# 8050a_led.net
KiCad netlist of a schematic drawn in EAGLE
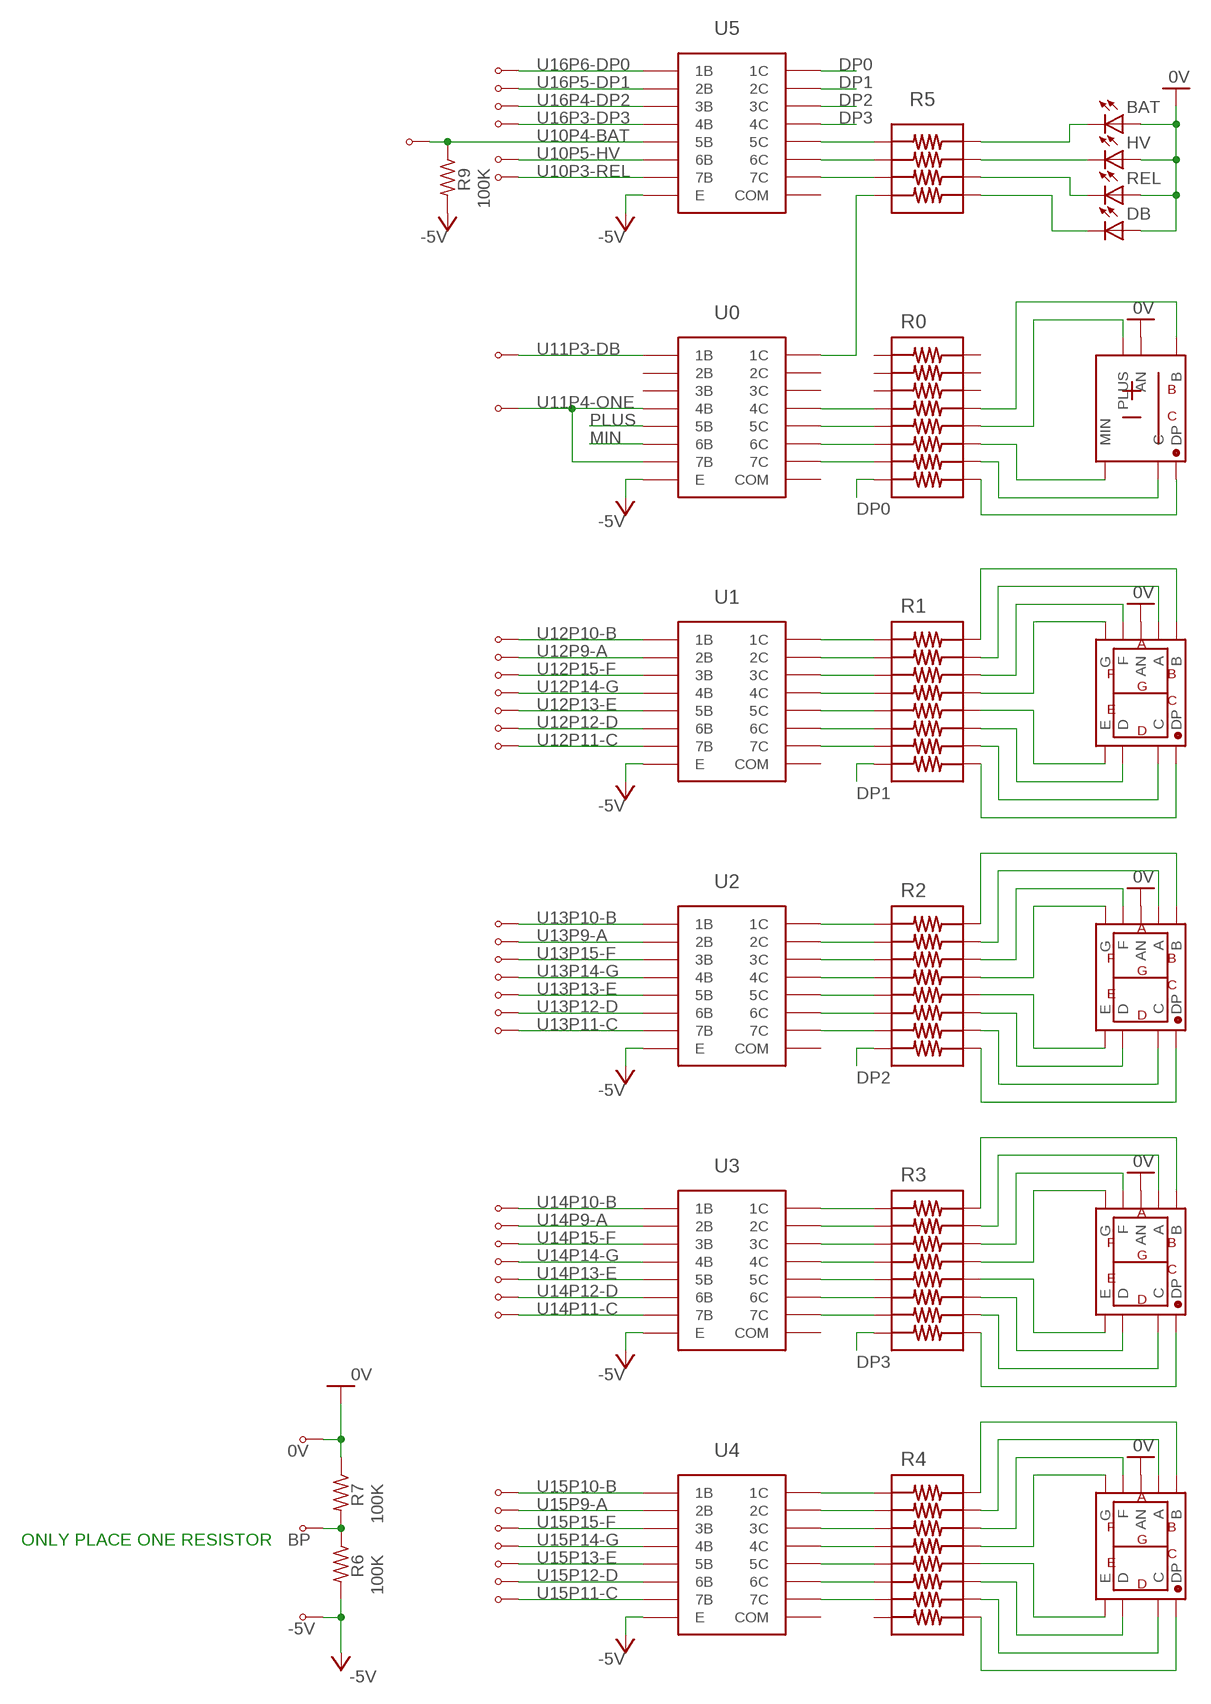
[diagram p0: schematic, sheet 1]

(export (version "E")
  (design (tool "Eeschema 10.0.6"))
  (components
    (comp (ref "BAT")
      (value "LED_0805")
      (footprint "eagle-import:0805_POL")
      (libsource (lib "eagle-import") (part "LED_0805"))
    )
    (comp (ref "D0")
      (value "LUMEX_LDF-A5616RI")
      (footprint "eagle-import:LUMEX_LDS-A516RI")
      (libsource (lib "eagle-import") (part "LUMEX_LDF-A5616RI"))
    )
    (comp (ref "D1")
      (value "LUMEX_LDS-A516RI")
      (footprint "eagle-import:LUMEX_LDS-A516RI")
      (libsource (lib "eagle-import") (part "LUMEX_LDS-A516RI"))
    )
    (comp (ref "D2")
      (value "LUMEX_LDS-A516RI")
      (footprint "eagle-import:LUMEX_LDS-A516RI")
      (libsource (lib "eagle-import") (part "LUMEX_LDS-A516RI"))
    )
    (comp (ref "D3")
      (value "LUMEX_LDS-A516RI")
      (footprint "eagle-import:LUMEX_LDS-A516RI")
      (libsource (lib "eagle-import") (part "LUMEX_LDS-A516RI"))
    )
    (comp (ref "D4")
      (value "LUMEX_LDS-A516RI")
      (footprint "eagle-import:LUMEX_LDS-A516RI")
      (libsource (lib "eagle-import") (part "LUMEX_LDS-A516RI"))
    )
    (comp (ref "DB")
      (value "LED_0805")
      (footprint "eagle-import:0805_POL")
      (libsource (lib "eagle-import") (part "LED_0805"))
    )
    (comp (ref "HV")
      (value "LED_0805")
      (footprint "eagle-import:0805_POL")
      (libsource (lib "eagle-import") (part "LED_0805"))
    )
    (comp (ref "R0")
      (value "BOURNS_CAT16-XXXJ8")
      (footprint "eagle-import:BOURNS_CAT16-J8")
      (libsource (lib "eagle-import") (part "BOURNS_CAT16-XXXJ8"))
    )
    (comp (ref "R1")
      (value "BOURNS_CAT16-XXXJ8")
      (footprint "eagle-import:BOURNS_CAT16-J8")
      (libsource (lib "eagle-import") (part "BOURNS_CAT16-XXXJ8"))
    )
    (comp (ref "R2")
      (value "BOURNS_CAT16-XXXJ8")
      (footprint "eagle-import:BOURNS_CAT16-J8")
      (libsource (lib "eagle-import") (part "BOURNS_CAT16-XXXJ8"))
    )
    (comp (ref "R3")
      (value "BOURNS_CAT16-XXXJ8")
      (footprint "eagle-import:BOURNS_CAT16-J8")
      (libsource (lib "eagle-import") (part "BOURNS_CAT16-XXXJ8"))
    )
    (comp (ref "R4")
      (value "BOURNS_CAT16-XXXJ8")
      (footprint "eagle-import:BOURNS_CAT16-J8")
      (libsource (lib "eagle-import") (part "BOURNS_CAT16-XXXJ8"))
    )
    (comp (ref "R5")
      (value "BOURNS_CAT16XXXJ4")
      (footprint "eagle-import:BOURNS_CAT16-J4")
      (libsource (lib "eagle-import") (part "BOURNS_CAT16XXXJ4"))
    )
    (comp (ref "R6")
      (value "100K")
      (footprint "eagle-import:0603")
      (libsource (lib "eagle-import") (part "R_0603"))
    )
    (comp (ref "R7")
      (value "100K")
      (footprint "eagle-import:0603")
      (libsource (lib "eagle-import") (part "R_0603"))
    )
    (comp (ref "R9")
      (value "100K")
      (footprint "eagle-import:0603")
      (libsource (lib "eagle-import") (part "R_0603"))
    )
    (comp (ref "REL")
      (value "LED_0805")
      (footprint "eagle-import:0805_POL")
      (libsource (lib "eagle-import") (part "LED_0805"))
    )
    (comp (ref "TP1")
      (value "KEYSTONE_500X")
      (footprint "eagle-import:KEYSTONE_500X")
      (libsource (lib "eagle-import") (part "KEYSTONE_500X"))
    )
    (comp (ref "TP2")
      (value "KEYSTONE_500X")
      (footprint "eagle-import:KEYSTONE_500X")
      (libsource (lib "eagle-import") (part "KEYSTONE_500X"))
    )
    (comp (ref "TP3")
      (value "KEYSTONE_500X")
      (footprint "eagle-import:KEYSTONE_500X")
      (libsource (lib "eagle-import") (part "KEYSTONE_500X"))
    )
    (comp (ref "TP4")
      (value "KEYSTONE_500X")
      (footprint "eagle-import:KEYSTONE_500X")
      (libsource (lib "eagle-import") (part "KEYSTONE_500X"))
    )
    (comp (ref "TP5")
      (value "KEYSTONE_500X")
      (footprint "eagle-import:KEYSTONE_500X")
      (libsource (lib "eagle-import") (part "KEYSTONE_500X"))
    )
    (comp (ref "TP6")
      (value "KEYSTONE_500X")
      (footprint "eagle-import:KEYSTONE_500X")
      (libsource (lib "eagle-import") (part "KEYSTONE_500X"))
    )
    (comp (ref "TP7")
      (value "KEYSTONE_500X")
      (footprint "eagle-import:KEYSTONE_500X")
      (libsource (lib "eagle-import") (part "KEYSTONE_500X"))
    )
    (comp (ref "TP8")
      (value "KEYSTONE_500X")
      (footprint "eagle-import:KEYSTONE_500X")
      (libsource (lib "eagle-import") (part "KEYSTONE_500X"))
    )
    (comp (ref "TP9")
      (value "KEYSTONE_500X")
      (footprint "eagle-import:KEYSTONE_500X")
      (libsource (lib "eagle-import") (part "KEYSTONE_500X"))
    )
    (comp (ref "TP10")
      (value "KEYSTONE_500X")
      (footprint "eagle-import:KEYSTONE_500X")
      (libsource (lib "eagle-import") (part "KEYSTONE_500X"))
    )
    (comp (ref "TP11")
      (value "KEYSTONE_500X")
      (footprint "eagle-import:KEYSTONE_500X")
      (libsource (lib "eagle-import") (part "KEYSTONE_500X"))
    )
    (comp (ref "TP12")
      (value "KEYSTONE_500X")
      (footprint "eagle-import:KEYSTONE_500X")
      (libsource (lib "eagle-import") (part "KEYSTONE_500X"))
    )
    (comp (ref "TP13")
      (value "KEYSTONE_500X")
      (footprint "eagle-import:KEYSTONE_500X")
      (libsource (lib "eagle-import") (part "KEYSTONE_500X"))
    )
    (comp (ref "TP14")
      (value "KEYSTONE_500X")
      (footprint "eagle-import:KEYSTONE_500X")
      (libsource (lib "eagle-import") (part "KEYSTONE_500X"))
    )
    (comp (ref "TP15")
      (value "KEYSTONE_500X")
      (footprint "eagle-import:KEYSTONE_500X")
      (libsource (lib "eagle-import") (part "KEYSTONE_500X"))
    )
    (comp (ref "TP16")
      (value "KEYSTONE_500X")
      (footprint "eagle-import:KEYSTONE_500X")
      (libsource (lib "eagle-import") (part "KEYSTONE_500X"))
    )
    (comp (ref "TP17")
      (value "KEYSTONE_500X")
      (footprint "eagle-import:KEYSTONE_500X")
      (libsource (lib "eagle-import") (part "KEYSTONE_500X"))
    )
    (comp (ref "TP18")
      (value "KEYSTONE_500X")
      (footprint "eagle-import:KEYSTONE_500X")
      (libsource (lib "eagle-import") (part "KEYSTONE_500X"))
    )
    (comp (ref "TP19")
      (value "KEYSTONE_500X")
      (footprint "eagle-import:KEYSTONE_500X")
      (libsource (lib "eagle-import") (part "KEYSTONE_500X"))
    )
    (comp (ref "TP20")
      (value "KEYSTONE_500X")
      (footprint "eagle-import:KEYSTONE_500X")
      (libsource (lib "eagle-import") (part "KEYSTONE_500X"))
    )
    (comp (ref "TP21")
      (value "KEYSTONE_500X")
      (footprint "eagle-import:KEYSTONE_500X")
      (libsource (lib "eagle-import") (part "KEYSTONE_500X"))
    )
    (comp (ref "TP22")
      (value "KEYSTONE_500X")
      (footprint "eagle-import:KEYSTONE_500X")
      (libsource (lib "eagle-import") (part "KEYSTONE_500X"))
    )
    (comp (ref "TP23")
      (value "KEYSTONE_500X")
      (footprint "eagle-import:KEYSTONE_500X")
      (libsource (lib "eagle-import") (part "KEYSTONE_500X"))
    )
    (comp (ref "TP24")
      (value "KEYSTONE_500X")
      (footprint "eagle-import:KEYSTONE_500X")
      (libsource (lib "eagle-import") (part "KEYSTONE_500X"))
    )
    (comp (ref "TP25")
      (value "KEYSTONE_500X")
      (footprint "eagle-import:KEYSTONE_500X")
      (libsource (lib "eagle-import") (part "KEYSTONE_500X"))
    )
    (comp (ref "TP26")
      (value "KEYSTONE_500X")
      (footprint "eagle-import:KEYSTONE_500X")
      (libsource (lib "eagle-import") (part "KEYSTONE_500X"))
    )
    (comp (ref "TP27")
      (value "KEYSTONE_500X")
      (footprint "eagle-import:KEYSTONE_500X")
      (libsource (lib "eagle-import") (part "KEYSTONE_500X"))
    )
    (comp (ref "TP28")
      (value "KEYSTONE_500X")
      (footprint "eagle-import:KEYSTONE_500X")
      (libsource (lib "eagle-import") (part "KEYSTONE_500X"))
    )
    (comp (ref "TP29")
      (value "KEYSTONE_500X")
      (footprint "eagle-import:KEYSTONE_500X")
      (libsource (lib "eagle-import") (part "KEYSTONE_500X"))
    )
    (comp (ref "TP30")
      (value "KEYSTONE_500X")
      (footprint "eagle-import:KEYSTONE_500X")
      (libsource (lib "eagle-import") (part "KEYSTONE_500X"))
    )
    (comp (ref "TP31")
      (value "KEYSTONE_500X")
      (footprint "eagle-import:KEYSTONE_500X")
      (libsource (lib "eagle-import") (part "KEYSTONE_500X"))
    )
    (comp (ref "TP32")
      (value "KEYSTONE_500X")
      (footprint "eagle-import:KEYSTONE_500X")
      (libsource (lib "eagle-import") (part "KEYSTONE_500X"))
    )
    (comp (ref "TP35")
      (value "KEYSTONE_500X")
      (footprint "eagle-import:KEYSTONE_500X")
      (libsource (lib "eagle-import") (part "KEYSTONE_500X"))
    )
    (comp (ref "TP36")
      (value "KEYSTONE_500X")
      (footprint "eagle-import:KEYSTONE_500X")
      (libsource (lib "eagle-import") (part "KEYSTONE_500X"))
    )
    (comp (ref "TP37")
      (value "KEYSTONE_500X")
      (footprint "eagle-import:KEYSTONE_500X")
      (libsource (lib "eagle-import") (part "KEYSTONE_500X"))
    )
    (comp (ref "TP38")
      (value "KEYSTONE_500X")
      (footprint "eagle-import:KEYSTONE_500X")
      (libsource (lib "eagle-import") (part "KEYSTONE_500X"))
    )
    (comp (ref "TP39")
      (value "KEYSTONE_500X")
      (footprint "eagle-import:KEYSTONE_500X")
      (libsource (lib "eagle-import") (part "KEYSTONE_500X"))
    )
    (comp (ref "TP40")
      (value "KEYSTONE_500X")
      (footprint "eagle-import:KEYSTONE_500X")
      (libsource (lib "eagle-import") (part "KEYSTONE_500X"))
    )
    (comp (ref "TP41")
      (value "KEYSTONE_500X")
      (footprint "eagle-import:KEYSTONE_500X")
      (libsource (lib "eagle-import") (part "KEYSTONE_500X"))
    )
    (comp (ref "TP42")
      (value "KEYSTONE_500X")
      (footprint "eagle-import:KEYSTONE_500X")
      (libsource (lib "eagle-import") (part "KEYSTONE_500X"))
    )
    (comp (ref "U0")
      (value "TI_ULN2003A")
      (footprint "eagle-import:SOIC16_TI")
      (libsource (lib "eagle-import") (part "TI_ULN2003A"))
    )
    (comp (ref "U1")
      (value "TI_ULN2003A")
      (footprint "eagle-import:SOIC16_TI")
      (libsource (lib "eagle-import") (part "TI_ULN2003A"))
    )
    (comp (ref "U2")
      (value "TI_ULN2003A")
      (footprint "eagle-import:SOIC16_TI")
      (libsource (lib "eagle-import") (part "TI_ULN2003A"))
    )
    (comp (ref "U3")
      (value "TI_ULN2003A")
      (footprint "eagle-import:SOIC16_TI")
      (libsource (lib "eagle-import") (part "TI_ULN2003A"))
    )
    (comp (ref "U4")
      (value "TI_ULN2003A")
      (footprint "eagle-import:SOIC16_TI")
      (libsource (lib "eagle-import") (part "TI_ULN2003A"))
    )
    (comp (ref "U5")
      (value "TI_ULN2003A")
      (footprint "eagle-import:SOIC16_TI")
      (libsource (lib "eagle-import") (part "TI_ULN2003A"))
    )
  )
  (nets
    (net (code "1") (name "-5V") (class "Default")
      (node (ref "R6") (pin "P$2") (pinfunction "2_P$2") (pintype "passive"))
      (node (ref "R9") (pin "P$2") (pinfunction "2_P$2") (pintype "passive"))
      (node (ref "TP8") (pin "P$1") (pinfunction "TP_P$1") (pintype "passive"))
      (node (ref "U0") (pin "P$8") (pinfunction "E_P$8") (pintype "bidirectional"))
      (node (ref "U1") (pin "P$8") (pinfunction "E_P$8") (pintype "bidirectional"))
      (node (ref "U2") (pin "P$8") (pinfunction "E_P$8") (pintype "bidirectional"))
      (node (ref "U3") (pin "P$8") (pinfunction "E_P$8") (pintype "bidirectional"))
      (node (ref "U4") (pin "P$8") (pinfunction "E_P$8") (pintype "bidirectional"))
      (node (ref "U5") (pin "P$8") (pinfunction "E_P$8") (pintype "bidirectional"))
    )
    (net (code "2") (name "/BP") (class "Default")
      (node (ref "R6") (pin "P$1") (pinfunction "1_P$1") (pintype "passive"))
      (node (ref "R7") (pin "P$2") (pinfunction "2_P$2") (pintype "passive"))
      (node (ref "TP35") (pin "P$1") (pinfunction "TP_P$1") (pintype "passive"))
    )
    (net (code "3") (name "/DP0") (class "Default")
      (node (ref "R0") (pin "P$8") (pinfunction "P$8_P$8") (pintype "passive"))
      (node (ref "U5") (pin "P$16") (pinfunction "1C_P$16") (pintype "bidirectional"))
    )
    (net (code "4") (name "/DP1") (class "Default")
      (node (ref "R1") (pin "P$8") (pinfunction "P$8_P$8") (pintype "passive"))
      (node (ref "U5") (pin "P$15") (pinfunction "2C_P$15") (pintype "bidirectional"))
    )
    (net (code "5") (name "/DP2") (class "Default")
      (node (ref "R2") (pin "P$8") (pinfunction "P$8_P$8") (pintype "passive"))
      (node (ref "U5") (pin "P$14") (pinfunction "3C_P$14") (pintype "bidirectional"))
    )
    (net (code "6") (name "/DP3") (class "Default")
      (node (ref "R3") (pin "P$8") (pinfunction "P$8_P$8") (pintype "passive"))
      (node (ref "U5") (pin "P$13") (pinfunction "4C_P$13") (pintype "bidirectional"))
    )
    (net (code "7") (name "/MIN") (class "Default")
      (node (ref "U0") (pin "P$6") (pinfunction "6B_P$6") (pintype "bidirectional"))
    )
    (net (code "8") (name "/PLUS") (class "Default")
      (node (ref "U0") (pin "P$5") (pinfunction "5B_P$5") (pintype "bidirectional"))
    )
    (net (code "9") (name "/U10P3-REL") (class "Default")
      (node (ref "TP42") (pin "P$1") (pinfunction "TP_P$1") (pintype "passive"))
      (node (ref "U5") (pin "P$7") (pinfunction "7B_P$7") (pintype "bidirectional"))
    )
    (net (code "10") (name "/U10P4-BAT") (class "Default")
      (node (ref "R9") (pin "P$1") (pinfunction "1_P$1") (pintype "passive"))
      (node (ref "TP40") (pin "P$1") (pinfunction "TP_P$1") (pintype "passive"))
      (node (ref "U5") (pin "P$5") (pinfunction "5B_P$5") (pintype "bidirectional"))
    )
    (net (code "11") (name "/U10P5-HV") (class "Default")
      (node (ref "TP41") (pin "P$1") (pinfunction "TP_P$1") (pintype "passive"))
      (node (ref "U5") (pin "P$6") (pinfunction "6B_P$6") (pintype "bidirectional"))
    )
    (net (code "12") (name "/U11P3-DB") (class "Default")
      (node (ref "TP32") (pin "P$1") (pinfunction "TP_P$1") (pintype "passive"))
      (node (ref "U0") (pin "P$1") (pinfunction "1B_P$1") (pintype "bidirectional"))
    )
    (net (code "13") (name "/U11P4-ONE") (class "Default")
      (node (ref "TP31") (pin "P$1") (pinfunction "TP_P$1") (pintype "passive"))
      (node (ref "U0") (pin "P$4") (pinfunction "4B_P$4") (pintype "bidirectional"))
      (node (ref "U0") (pin "P$7") (pinfunction "7B_P$7") (pintype "bidirectional"))
    )
    (net (code "14") (name "/U12P9-A") (class "Default")
      (node (ref "TP2") (pin "P$1") (pinfunction "TP_P$1") (pintype "passive"))
      (node (ref "U1") (pin "P$2") (pinfunction "2B_P$2") (pintype "bidirectional"))
    )
    (net (code "15") (name "/U12P10-B") (class "Default")
      (node (ref "TP1") (pin "P$1") (pinfunction "TP_P$1") (pintype "passive"))
      (node (ref "U1") (pin "P$1") (pinfunction "1B_P$1") (pintype "bidirectional"))
    )
    (net (code "16") (name "/U12P11-C") (class "Default")
      (node (ref "TP7") (pin "P$1") (pinfunction "TP_P$1") (pintype "passive"))
      (node (ref "U1") (pin "P$7") (pinfunction "7B_P$7") (pintype "bidirectional"))
    )
    (net (code "17") (name "/U12P12-D") (class "Default")
      (node (ref "TP6") (pin "P$1") (pinfunction "TP_P$1") (pintype "passive"))
      (node (ref "U1") (pin "P$6") (pinfunction "6B_P$6") (pintype "bidirectional"))
    )
    (net (code "18") (name "/U12P13-E") (class "Default")
      (node (ref "TP5") (pin "P$1") (pinfunction "TP_P$1") (pintype "passive"))
      (node (ref "U1") (pin "P$5") (pinfunction "5B_P$5") (pintype "bidirectional"))
    )
    (net (code "19") (name "/U12P14-G") (class "Default")
      (node (ref "TP4") (pin "P$1") (pinfunction "TP_P$1") (pintype "passive"))
      (node (ref "U1") (pin "P$4") (pinfunction "4B_P$4") (pintype "bidirectional"))
    )
    (net (code "20") (name "/U12P15-F") (class "Default")
      (node (ref "TP3") (pin "P$1") (pinfunction "TP_P$1") (pintype "passive"))
      (node (ref "U1") (pin "P$3") (pinfunction "3B_P$3") (pintype "bidirectional"))
    )
    (net (code "21") (name "/U13P9-A") (class "Default")
      (node (ref "TP11") (pin "P$1") (pinfunction "TP_P$1") (pintype "passive"))
      (node (ref "U2") (pin "P$2") (pinfunction "2B_P$2") (pintype "bidirectional"))
    )
    (net (code "22") (name "/U13P10-B") (class "Default")
      (node (ref "TP10") (pin "P$1") (pinfunction "TP_P$1") (pintype "passive"))
      (node (ref "U2") (pin "P$1") (pinfunction "1B_P$1") (pintype "bidirectional"))
    )
    (net (code "23") (name "/U13P11-C") (class "Default")
      (node (ref "TP16") (pin "P$1") (pinfunction "TP_P$1") (pintype "passive"))
      (node (ref "U2") (pin "P$7") (pinfunction "7B_P$7") (pintype "bidirectional"))
    )
    (net (code "24") (name "/U13P12-D") (class "Default")
      (node (ref "TP15") (pin "P$1") (pinfunction "TP_P$1") (pintype "passive"))
      (node (ref "U2") (pin "P$6") (pinfunction "6B_P$6") (pintype "bidirectional"))
    )
    (net (code "25") (name "/U13P13-E") (class "Default")
      (node (ref "TP14") (pin "P$1") (pinfunction "TP_P$1") (pintype "passive"))
      (node (ref "U2") (pin "P$5") (pinfunction "5B_P$5") (pintype "bidirectional"))
    )
    (net (code "26") (name "/U13P14-G") (class "Default")
      (node (ref "TP13") (pin "P$1") (pinfunction "TP_P$1") (pintype "passive"))
      (node (ref "U2") (pin "P$4") (pinfunction "4B_P$4") (pintype "bidirectional"))
    )
    (net (code "27") (name "/U13P15-F") (class "Default")
      (node (ref "TP12") (pin "P$1") (pinfunction "TP_P$1") (pintype "passive"))
      (node (ref "U2") (pin "P$3") (pinfunction "3B_P$3") (pintype "bidirectional"))
    )
    (net (code "28") (name "/U14P9-A") (class "Default")
      (node (ref "TP18") (pin "P$1") (pinfunction "TP_P$1") (pintype "passive"))
      (node (ref "U3") (pin "P$2") (pinfunction "2B_P$2") (pintype "bidirectional"))
    )
    (net (code "29") (name "/U14P10-B") (class "Default")
      (node (ref "TP17") (pin "P$1") (pinfunction "TP_P$1") (pintype "passive"))
      (node (ref "U3") (pin "P$1") (pinfunction "1B_P$1") (pintype "bidirectional"))
    )
    (net (code "30") (name "/U14P11-C") (class "Default")
      (node (ref "TP23") (pin "P$1") (pinfunction "TP_P$1") (pintype "passive"))
      (node (ref "U3") (pin "P$7") (pinfunction "7B_P$7") (pintype "bidirectional"))
    )
    (net (code "31") (name "/U14P12-D") (class "Default")
      (node (ref "TP22") (pin "P$1") (pinfunction "TP_P$1") (pintype "passive"))
      (node (ref "U3") (pin "P$6") (pinfunction "6B_P$6") (pintype "bidirectional"))
    )
    (net (code "32") (name "/U14P13-E") (class "Default")
      (node (ref "TP21") (pin "P$1") (pinfunction "TP_P$1") (pintype "passive"))
      (node (ref "U3") (pin "P$5") (pinfunction "5B_P$5") (pintype "bidirectional"))
    )
    (net (code "33") (name "/U14P14-G") (class "Default")
      (node (ref "TP20") (pin "P$1") (pinfunction "TP_P$1") (pintype "passive"))
      (node (ref "U3") (pin "P$4") (pinfunction "4B_P$4") (pintype "bidirectional"))
    )
    (net (code "34") (name "/U14P15-F") (class "Default")
      (node (ref "TP19") (pin "P$1") (pinfunction "TP_P$1") (pintype "passive"))
      (node (ref "U3") (pin "P$3") (pinfunction "3B_P$3") (pintype "bidirectional"))
    )
    (net (code "35") (name "/U15P9-A") (class "Default")
      (node (ref "TP25") (pin "P$1") (pinfunction "TP_P$1") (pintype "passive"))
      (node (ref "U4") (pin "P$2") (pinfunction "2B_P$2") (pintype "bidirectional"))
    )
    (net (code "36") (name "/U15P10-B") (class "Default")
      (node (ref "TP24") (pin "P$1") (pinfunction "TP_P$1") (pintype "passive"))
      (node (ref "U4") (pin "P$1") (pinfunction "1B_P$1") (pintype "bidirectional"))
    )
    (net (code "37") (name "/U15P11-C") (class "Default")
      (node (ref "TP30") (pin "P$1") (pinfunction "TP_P$1") (pintype "passive"))
      (node (ref "U4") (pin "P$7") (pinfunction "7B_P$7") (pintype "bidirectional"))
    )
    (net (code "38") (name "/U15P12-D") (class "Default")
      (node (ref "TP29") (pin "P$1") (pinfunction "TP_P$1") (pintype "passive"))
      (node (ref "U4") (pin "P$6") (pinfunction "6B_P$6") (pintype "bidirectional"))
    )
    (net (code "39") (name "/U15P13-E") (class "Default")
      (node (ref "TP28") (pin "P$1") (pinfunction "TP_P$1") (pintype "passive"))
      (node (ref "U4") (pin "P$5") (pinfunction "5B_P$5") (pintype "bidirectional"))
    )
    (net (code "40") (name "/U15P14-G") (class "Default")
      (node (ref "TP27") (pin "P$1") (pinfunction "TP_P$1") (pintype "passive"))
      (node (ref "U4") (pin "P$4") (pinfunction "4B_P$4") (pintype "bidirectional"))
    )
    (net (code "41") (name "/U15P15-F") (class "Default")
      (node (ref "TP26") (pin "P$1") (pinfunction "TP_P$1") (pintype "passive"))
      (node (ref "U4") (pin "P$3") (pinfunction "3B_P$3") (pintype "bidirectional"))
    )
    (net (code "42") (name "/U16P3-DP3") (class "Default")
      (node (ref "TP39") (pin "P$1") (pinfunction "TP_P$1") (pintype "passive"))
      (node (ref "U5") (pin "P$4") (pinfunction "4B_P$4") (pintype "bidirectional"))
    )
    (net (code "43") (name "/U16P4-DP2") (class "Default")
      (node (ref "TP38") (pin "P$1") (pinfunction "TP_P$1") (pintype "passive"))
      (node (ref "U5") (pin "P$3") (pinfunction "3B_P$3") (pintype "bidirectional"))
    )
    (net (code "44") (name "/U16P5-DP1") (class "Default")
      (node (ref "TP37") (pin "P$1") (pinfunction "TP_P$1") (pintype "passive"))
      (node (ref "U5") (pin "P$2") (pinfunction "2B_P$2") (pintype "bidirectional"))
    )
    (net (code "45") (name "/U16P6-DP0") (class "Default")
      (node (ref "TP36") (pin "P$1") (pinfunction "TP_P$1") (pintype "passive"))
      (node (ref "U5") (pin "P$1") (pinfunction "1B_P$1") (pintype "bidirectional"))
    )
    (net (code "46") (name "0V") (class "Default")
      (node (ref "BAT") (pin "P$1") (pinfunction "A_P$1") (pintype "passive"))
      (node (ref "D0") (pin "P$3") (pinfunction "AN_P$3") (pintype "bidirectional"))
      (node (ref "D0") (pin "P$8") (pinfunction "AN_P$8") (pintype "bidirectional"))
      (node (ref "D1") (pin "P$3") (pinfunction "AN_P$3") (pintype "bidirectional"))
      (node (ref "D1") (pin "P$8") (pinfunction "AN_P$8") (pintype "bidirectional"))
      (node (ref "D2") (pin "P$3") (pinfunction "AN_P$3") (pintype "bidirectional"))
      (node (ref "D2") (pin "P$8") (pinfunction "AN_P$8") (pintype "bidirectional"))
      (node (ref "D3") (pin "P$3") (pinfunction "AN_P$3") (pintype "bidirectional"))
      (node (ref "D3") (pin "P$8") (pinfunction "AN_P$8") (pintype "bidirectional"))
      (node (ref "D4") (pin "P$3") (pinfunction "AN_P$3") (pintype "bidirectional"))
      (node (ref "D4") (pin "P$8") (pinfunction "AN_P$8") (pintype "bidirectional"))
      (node (ref "DB") (pin "P$1") (pinfunction "A_P$1") (pintype "passive"))
      (node (ref "HV") (pin "P$1") (pinfunction "A_P$1") (pintype "passive"))
      (node (ref "R7") (pin "P$1") (pinfunction "1_P$1") (pintype "passive"))
      (node (ref "REL") (pin "P$1") (pinfunction "A_P$1") (pintype "passive"))
      (node (ref "TP9") (pin "P$1") (pinfunction "TP_P$1") (pintype "passive"))
    )
    (net (code "47") (name "Net-(BAT-C)") (class "Default")
      (node (ref "BAT") (pin "P$2") (pinfunction "C_P$2") (pintype "passive"))
      (node (ref "R5") (pin "P$8") (pinfunction "P$8_P$8") (pintype "passive"))
    )
    (net (code "48") (name "Net-(D0-B)") (class "Default")
      (node (ref "D0") (pin "P$6") (pinfunction "B_P$6") (pintype "bidirectional"))
      (node (ref "R0") (pin "P$13") (pinfunction "P$13_P$13") (pintype "passive"))
    )
    (net (code "49") (name "Net-(D0-C)") (class "Default")
      (node (ref "D0") (pin "P$4") (pinfunction "C_P$4") (pintype "bidirectional"))
      (node (ref "R0") (pin "P$10") (pinfunction "P$10_P$10") (pintype "passive"))
    )
    (net (code "50") (name "Net-(D0-DP)") (class "Default")
      (node (ref "D0") (pin "P$5") (pinfunction "DP_P$5") (pintype "bidirectional"))
      (node (ref "R0") (pin "P$9") (pinfunction "P$9_P$9") (pintype "passive"))
    )
    (net (code "51") (name "Net-(D0-MIN)") (class "Default")
      (node (ref "D0") (pin "P$1") (pinfunction "MIN_P$1") (pintype "bidirectional"))
      (node (ref "R0") (pin "P$11") (pinfunction "P$11_P$11") (pintype "passive"))
    )
    (net (code "52") (name "Net-(D0-PLUS)") (class "Default")
      (node (ref "D0") (pin "P$9") (pinfunction "PLUS_P$9") (pintype "bidirectional"))
      (node (ref "R0") (pin "P$12") (pinfunction "P$12_P$12") (pintype "passive"))
    )
    (net (code "53") (name "Net-(D1-A)") (class "Default")
      (node (ref "D1") (pin "P$7") (pinfunction "A_P$7") (pintype "bidirectional"))
      (node (ref "R1") (pin "P$15") (pinfunction "P$15_P$15") (pintype "passive"))
    )
    (net (code "54") (name "Net-(D1-B)") (class "Default")
      (node (ref "D1") (pin "P$6") (pinfunction "B_P$6") (pintype "bidirectional"))
      (node (ref "R1") (pin "P$16") (pinfunction "P$16_P$16") (pintype "passive"))
    )
    (net (code "55") (name "Net-(D1-C)") (class "Default")
      (node (ref "D1") (pin "P$4") (pinfunction "C_P$4") (pintype "bidirectional"))
      (node (ref "R1") (pin "P$10") (pinfunction "P$10_P$10") (pintype "passive"))
    )
    (net (code "56") (name "Net-(D1-D)") (class "Default")
      (node (ref "D1") (pin "P$2") (pinfunction "D_P$2") (pintype "bidirectional"))
      (node (ref "R1") (pin "P$11") (pinfunction "P$11_P$11") (pintype "passive"))
    )
    (net (code "57") (name "Net-(D1-DP)") (class "Default")
      (node (ref "D1") (pin "P$5") (pinfunction "DP_P$5") (pintype "bidirectional"))
      (node (ref "R1") (pin "P$9") (pinfunction "P$9_P$9") (pintype "passive"))
    )
    (net (code "58") (name "Net-(D1-E)") (class "Default")
      (node (ref "D1") (pin "P$1") (pinfunction "E_P$1") (pintype "bidirectional"))
      (node (ref "R1") (pin "P$12") (pinfunction "P$12_P$12") (pintype "passive"))
    )
    (net (code "59") (name "Net-(D1-F)") (class "Default")
      (node (ref "D1") (pin "P$9") (pinfunction "F_P$9") (pintype "bidirectional"))
      (node (ref "R1") (pin "P$14") (pinfunction "P$14_P$14") (pintype "passive"))
    )
    (net (code "60") (name "Net-(D1-G)") (class "Default")
      (node (ref "D1") (pin "P$10") (pinfunction "G_P$10") (pintype "bidirectional"))
      (node (ref "R1") (pin "P$13") (pinfunction "P$13_P$13") (pintype "passive"))
    )
    (net (code "61") (name "Net-(D2-A)") (class "Default")
      (node (ref "D2") (pin "P$7") (pinfunction "A_P$7") (pintype "bidirectional"))
      (node (ref "R2") (pin "P$15") (pinfunction "P$15_P$15") (pintype "passive"))
    )
    (net (code "62") (name "Net-(D2-B)") (class "Default")
      (node (ref "D2") (pin "P$6") (pinfunction "B_P$6") (pintype "bidirectional"))
      (node (ref "R2") (pin "P$16") (pinfunction "P$16_P$16") (pintype "passive"))
    )
    (net (code "63") (name "Net-(D2-C)") (class "Default")
      (node (ref "D2") (pin "P$4") (pinfunction "C_P$4") (pintype "bidirectional"))
      (node (ref "R2") (pin "P$10") (pinfunction "P$10_P$10") (pintype "passive"))
    )
    (net (code "64") (name "Net-(D2-D)") (class "Default")
      (node (ref "D2") (pin "P$2") (pinfunction "D_P$2") (pintype "bidirectional"))
      (node (ref "R2") (pin "P$11") (pinfunction "P$11_P$11") (pintype "passive"))
    )
    (net (code "65") (name "Net-(D2-DP)") (class "Default")
      (node (ref "D2") (pin "P$5") (pinfunction "DP_P$5") (pintype "bidirectional"))
      (node (ref "R2") (pin "P$9") (pinfunction "P$9_P$9") (pintype "passive"))
    )
    (net (code "66") (name "Net-(D2-E)") (class "Default")
      (node (ref "D2") (pin "P$1") (pinfunction "E_P$1") (pintype "bidirectional"))
      (node (ref "R2") (pin "P$12") (pinfunction "P$12_P$12") (pintype "passive"))
    )
    (net (code "67") (name "Net-(D2-F)") (class "Default")
      (node (ref "D2") (pin "P$9") (pinfunction "F_P$9") (pintype "bidirectional"))
      (node (ref "R2") (pin "P$14") (pinfunction "P$14_P$14") (pintype "passive"))
    )
    (net (code "68") (name "Net-(D2-G)") (class "Default")
      (node (ref "D2") (pin "P$10") (pinfunction "G_P$10") (pintype "bidirectional"))
      (node (ref "R2") (pin "P$13") (pinfunction "P$13_P$13") (pintype "passive"))
    )
    (net (code "69") (name "Net-(D3-A)") (class "Default")
      (node (ref "D3") (pin "P$7") (pinfunction "A_P$7") (pintype "bidirectional"))
      (node (ref "R3") (pin "P$15") (pinfunction "P$15_P$15") (pintype "passive"))
    )
    (net (code "70") (name "Net-(D3-B)") (class "Default")
      (node (ref "D3") (pin "P$6") (pinfunction "B_P$6") (pintype "bidirectional"))
      (node (ref "R3") (pin "P$16") (pinfunction "P$16_P$16") (pintype "passive"))
    )
    (net (code "71") (name "Net-(D3-C)") (class "Default")
      (node (ref "D3") (pin "P$4") (pinfunction "C_P$4") (pintype "bidirectional"))
      (node (ref "R3") (pin "P$10") (pinfunction "P$10_P$10") (pintype "passive"))
    )
    (net (code "72") (name "Net-(D3-D)") (class "Default")
      (node (ref "D3") (pin "P$2") (pinfunction "D_P$2") (pintype "bidirectional"))
      (node (ref "R3") (pin "P$11") (pinfunction "P$11_P$11") (pintype "passive"))
    )
    (net (code "73") (name "Net-(D3-DP)") (class "Default")
      (node (ref "D3") (pin "P$5") (pinfunction "DP_P$5") (pintype "bidirectional"))
      (node (ref "R3") (pin "P$9") (pinfunction "P$9_P$9") (pintype "passive"))
    )
    (net (code "74") (name "Net-(D3-E)") (class "Default")
      (node (ref "D3") (pin "P$1") (pinfunction "E_P$1") (pintype "bidirectional"))
      (node (ref "R3") (pin "P$12") (pinfunction "P$12_P$12") (pintype "passive"))
    )
    (net (code "75") (name "Net-(D3-F)") (class "Default")
      (node (ref "D3") (pin "P$9") (pinfunction "F_P$9") (pintype "bidirectional"))
      (node (ref "R3") (pin "P$14") (pinfunction "P$14_P$14") (pintype "passive"))
    )
    (net (code "76") (name "Net-(D3-G)") (class "Default")
      (node (ref "D3") (pin "P$10") (pinfunction "G_P$10") (pintype "bidirectional"))
      (node (ref "R3") (pin "P$13") (pinfunction "P$13_P$13") (pintype "passive"))
    )
    (net (code "77") (name "Net-(D4-A)") (class "Default")
      (node (ref "D4") (pin "P$7") (pinfunction "A_P$7") (pintype "bidirectional"))
      (node (ref "R4") (pin "P$15") (pinfunction "P$15_P$15") (pintype "passive"))
    )
    (net (code "78") (name "Net-(D4-B)") (class "Default")
      (node (ref "D4") (pin "P$6") (pinfunction "B_P$6") (pintype "bidirectional"))
      (node (ref "R4") (pin "P$16") (pinfunction "P$16_P$16") (pintype "passive"))
    )
    (net (code "79") (name "Net-(D4-C)") (class "Default")
      (node (ref "D4") (pin "P$4") (pinfunction "C_P$4") (pintype "bidirectional"))
      (node (ref "R4") (pin "P$10") (pinfunction "P$10_P$10") (pintype "passive"))
    )
    (net (code "80") (name "Net-(D4-D)") (class "Default")
      (node (ref "D4") (pin "P$2") (pinfunction "D_P$2") (pintype "bidirectional"))
      (node (ref "R4") (pin "P$11") (pinfunction "P$11_P$11") (pintype "passive"))
    )
    (net (code "81") (name "Net-(D4-DP)") (class "Default")
      (node (ref "D4") (pin "P$5") (pinfunction "DP_P$5") (pintype "bidirectional"))
      (node (ref "R4") (pin "P$9") (pinfunction "P$9_P$9") (pintype "passive"))
    )
    (net (code "82") (name "Net-(D4-E)") (class "Default")
      (node (ref "D4") (pin "P$1") (pinfunction "E_P$1") (pintype "bidirectional"))
      (node (ref "R4") (pin "P$12") (pinfunction "P$12_P$12") (pintype "passive"))
    )
    (net (code "83") (name "Net-(D4-F)") (class "Default")
      (node (ref "D4") (pin "P$9") (pinfunction "F_P$9") (pintype "bidirectional"))
      (node (ref "R4") (pin "P$14") (pinfunction "P$14_P$14") (pintype "passive"))
    )
    (net (code "84") (name "Net-(D4-G)") (class "Default")
      (node (ref "D4") (pin "P$10") (pinfunction "G_P$10") (pintype "bidirectional"))
      (node (ref "R4") (pin "P$13") (pinfunction "P$13_P$13") (pintype "passive"))
    )
    (net (code "85") (name "Net-(DB-C)") (class "Default")
      (node (ref "DB") (pin "P$2") (pinfunction "C_P$2") (pintype "passive"))
      (node (ref "R5") (pin "P$5") (pinfunction "P$5_P$5") (pintype "passive"))
    )
    (net (code "86") (name "Net-(HV-C)") (class "Default")
      (node (ref "HV") (pin "P$2") (pinfunction "C_P$2") (pintype "passive"))
      (node (ref "R5") (pin "P$7") (pinfunction "P$7_P$7") (pintype "passive"))
    )
    (net (code "87") (name "Net-(REL-C)") (class "Default")
      (node (ref "R5") (pin "P$6") (pinfunction "P$6_P$6") (pintype "passive"))
      (node (ref "REL") (pin "P$2") (pinfunction "C_P$2") (pintype "passive"))
    )
    (net (code "88") (name "Net-(U0-1C)") (class "Default")
      (node (ref "R5") (pin "P$4") (pinfunction "P$4_P$4") (pintype "passive"))
      (node (ref "U0") (pin "P$16") (pinfunction "1C_P$16") (pintype "bidirectional"))
    )
    (net (code "89") (name "Net-(U0-4C)") (class "Default")
      (node (ref "R0") (pin "P$4") (pinfunction "P$4_P$4") (pintype "passive"))
      (node (ref "U0") (pin "P$13") (pinfunction "4C_P$13") (pintype "bidirectional"))
    )
    (net (code "90") (name "Net-(U0-5C)") (class "Default")
      (node (ref "R0") (pin "P$5") (pinfunction "P$5_P$5") (pintype "passive"))
      (node (ref "U0") (pin "P$12") (pinfunction "5C_P$12") (pintype "bidirectional"))
    )
    (net (code "91") (name "Net-(U0-6C)") (class "Default")
      (node (ref "R0") (pin "P$6") (pinfunction "P$6_P$6") (pintype "passive"))
      (node (ref "U0") (pin "P$11") (pinfunction "6C_P$11") (pintype "bidirectional"))
    )
    (net (code "92") (name "Net-(U0-7C)") (class "Default")
      (node (ref "R0") (pin "P$7") (pinfunction "P$7_P$7") (pintype "passive"))
      (node (ref "U0") (pin "P$10") (pinfunction "7C_P$10") (pintype "bidirectional"))
    )
    (net (code "93") (name "Net-(U1-1C)") (class "Default")
      (node (ref "R1") (pin "P$1") (pinfunction "P$1_P$1") (pintype "passive"))
      (node (ref "U1") (pin "P$16") (pinfunction "1C_P$16") (pintype "bidirectional"))
    )
    (net (code "94") (name "Net-(U1-2C)") (class "Default")
      (node (ref "R1") (pin "P$2") (pinfunction "P$2_P$2") (pintype "passive"))
      (node (ref "U1") (pin "P$15") (pinfunction "2C_P$15") (pintype "bidirectional"))
    )
    (net (code "95") (name "Net-(U1-3C)") (class "Default")
      (node (ref "R1") (pin "P$3") (pinfunction "P$3_P$3") (pintype "passive"))
      (node (ref "U1") (pin "P$14") (pinfunction "3C_P$14") (pintype "bidirectional"))
    )
    (net (code "96") (name "Net-(U1-4C)") (class "Default")
      (node (ref "R1") (pin "P$4") (pinfunction "P$4_P$4") (pintype "passive"))
      (node (ref "U1") (pin "P$13") (pinfunction "4C_P$13") (pintype "bidirectional"))
    )
    (net (code "97") (name "Net-(U1-5C)") (class "Default")
      (node (ref "R1") (pin "P$5") (pinfunction "P$5_P$5") (pintype "passive"))
      (node (ref "U1") (pin "P$12") (pinfunction "5C_P$12") (pintype "bidirectional"))
    )
    (net (code "98") (name "Net-(U1-6C)") (class "Default")
      (node (ref "R1") (pin "P$6") (pinfunction "P$6_P$6") (pintype "passive"))
      (node (ref "U1") (pin "P$11") (pinfunction "6C_P$11") (pintype "bidirectional"))
    )
    (net (code "99") (name "Net-(U1-7C)") (class "Default")
      (node (ref "R1") (pin "P$7") (pinfunction "P$7_P$7") (pintype "passive"))
      (node (ref "U1") (pin "P$10") (pinfunction "7C_P$10") (pintype "bidirectional"))
    )
    (net (code "100") (name "Net-(U2-1C)") (class "Default")
      (node (ref "R2") (pin "P$1") (pinfunction "P$1_P$1") (pintype "passive"))
      (node (ref "U2") (pin "P$16") (pinfunction "1C_P$16") (pintype "bidirectional"))
    )
    (net (code "101") (name "Net-(U2-2C)") (class "Default")
      (node (ref "R2") (pin "P$2") (pinfunction "P$2_P$2") (pintype "passive"))
      (node (ref "U2") (pin "P$15") (pinfunction "2C_P$15") (pintype "bidirectional"))
    )
    (net (code "102") (name "Net-(U2-3C)") (class "Default")
      (node (ref "R2") (pin "P$3") (pinfunction "P$3_P$3") (pintype "passive"))
      (node (ref "U2") (pin "P$14") (pinfunction "3C_P$14") (pintype "bidirectional"))
    )
    (net (code "103") (name "Net-(U2-4C)") (class "Default")
      (node (ref "R2") (pin "P$4") (pinfunction "P$4_P$4") (pintype "passive"))
      (node (ref "U2") (pin "P$13") (pinfunction "4C_P$13") (pintype "bidirectional"))
    )
    (net (code "104") (name "Net-(U2-5C)") (class "Default")
      (node (ref "R2") (pin "P$5") (pinfunction "P$5_P$5") (pintype "passive"))
      (node (ref "U2") (pin "P$12") (pinfunction "5C_P$12") (pintype "bidirectional"))
    )
    (net (code "105") (name "Net-(U2-6C)") (class "Default")
      (node (ref "R2") (pin "P$6") (pinfunction "P$6_P$6") (pintype "passive"))
      (node (ref "U2") (pin "P$11") (pinfunction "6C_P$11") (pintype "bidirectional"))
    )
    (net (code "106") (name "Net-(U2-7C)") (class "Default")
      (node (ref "R2") (pin "P$7") (pinfunction "P$7_P$7") (pintype "passive"))
      (node (ref "U2") (pin "P$10") (pinfunction "7C_P$10") (pintype "bidirectional"))
    )
    (net (code "107") (name "Net-(U3-1C)") (class "Default")
      (node (ref "R3") (pin "P$1") (pinfunction "P$1_P$1") (pintype "passive"))
      (node (ref "U3") (pin "P$16") (pinfunction "1C_P$16") (pintype "bidirectional"))
    )
    (net (code "108") (name "Net-(U3-2C)") (class "Default")
      (node (ref "R3") (pin "P$2") (pinfunction "P$2_P$2") (pintype "passive"))
      (node (ref "U3") (pin "P$15") (pinfunction "2C_P$15") (pintype "bidirectional"))
    )
    (net (code "109") (name "Net-(U3-3C)") (class "Default")
      (node (ref "R3") (pin "P$3") (pinfunction "P$3_P$3") (pintype "passive"))
      (node (ref "U3") (pin "P$14") (pinfunction "3C_P$14") (pintype "bidirectional"))
    )
    (net (code "110") (name "Net-(U3-4C)") (class "Default")
      (node (ref "R3") (pin "P$4") (pinfunction "P$4_P$4") (pintype "passive"))
      (node (ref "U3") (pin "P$13") (pinfunction "4C_P$13") (pintype "bidirectional"))
    )
    (net (code "111") (name "Net-(U3-5C)") (class "Default")
      (node (ref "R3") (pin "P$5") (pinfunction "P$5_P$5") (pintype "passive"))
      (node (ref "U3") (pin "P$12") (pinfunction "5C_P$12") (pintype "bidirectional"))
    )
    (net (code "112") (name "Net-(U3-6C)") (class "Default")
      (node (ref "R3") (pin "P$6") (pinfunction "P$6_P$6") (pintype "passive"))
      (node (ref "U3") (pin "P$11") (pinfunction "6C_P$11") (pintype "bidirectional"))
    )
    (net (code "113") (name "Net-(U3-7C)") (class "Default")
      (node (ref "R3") (pin "P$7") (pinfunction "P$7_P$7") (pintype "passive"))
      (node (ref "U3") (pin "P$10") (pinfunction "7C_P$10") (pintype "bidirectional"))
    )
    (net (code "114") (name "Net-(U4-1C)") (class "Default")
      (node (ref "R4") (pin "P$1") (pinfunction "P$1_P$1") (pintype "passive"))
      (node (ref "U4") (pin "P$16") (pinfunction "1C_P$16") (pintype "bidirectional"))
    )
    (net (code "115") (name "Net-(U4-2C)") (class "Default")
      (node (ref "R4") (pin "P$2") (pinfunction "P$2_P$2") (pintype "passive"))
      (node (ref "U4") (pin "P$15") (pinfunction "2C_P$15") (pintype "bidirectional"))
    )
    (net (code "116") (name "Net-(U4-3C)") (class "Default")
      (node (ref "R4") (pin "P$3") (pinfunction "P$3_P$3") (pintype "passive"))
      (node (ref "U4") (pin "P$14") (pinfunction "3C_P$14") (pintype "bidirectional"))
    )
    (net (code "117") (name "Net-(U4-4C)") (class "Default")
      (node (ref "R4") (pin "P$4") (pinfunction "P$4_P$4") (pintype "passive"))
      (node (ref "U4") (pin "P$13") (pinfunction "4C_P$13") (pintype "bidirectional"))
    )
    (net (code "118") (name "Net-(U4-5C)") (class "Default")
      (node (ref "R4") (pin "P$5") (pinfunction "P$5_P$5") (pintype "passive"))
      (node (ref "U4") (pin "P$12") (pinfunction "5C_P$12") (pintype "bidirectional"))
    )
    (net (code "119") (name "Net-(U4-6C)") (class "Default")
      (node (ref "R4") (pin "P$6") (pinfunction "P$6_P$6") (pintype "passive"))
      (node (ref "U4") (pin "P$11") (pinfunction "6C_P$11") (pintype "bidirectional"))
    )
    (net (code "120") (name "Net-(U4-7C)") (class "Default")
      (node (ref "R4") (pin "P$7") (pinfunction "P$7_P$7") (pintype "passive"))
      (node (ref "U4") (pin "P$10") (pinfunction "7C_P$10") (pintype "bidirectional"))
    )
    (net (code "121") (name "Net-(U5-5C)") (class "Default")
      (node (ref "R5") (pin "P$1") (pinfunction "P$1_P$1") (pintype "passive"))
      (node (ref "U5") (pin "P$12") (pinfunction "5C_P$12") (pintype "bidirectional"))
    )
    (net (code "122") (name "Net-(U5-6C)") (class "Default")
      (node (ref "R5") (pin "P$2") (pinfunction "P$2_P$2") (pintype "passive"))
      (node (ref "U5") (pin "P$11") (pinfunction "6C_P$11") (pintype "bidirectional"))
    )
    (net (code "123") (name "Net-(U5-7C)") (class "Default")
      (node (ref "R5") (pin "P$3") (pinfunction "P$3_P$3") (pintype "passive"))
      (node (ref "U5") (pin "P$10") (pinfunction "7C_P$10") (pintype "bidirectional"))
    )
    (net (code "124") (name "unconnected-(R0-PadP$1)") (class "Default")
      (node (ref "R0") (pin "P$1") (pinfunction "P$1_P$1") (pintype "passive"))
    )
    (net (code "125") (name "unconnected-(R0-PadP$2)") (class "Default")
      (node (ref "R0") (pin "P$2") (pinfunction "P$2_P$2") (pintype "passive"))
    )
    (net (code "126") (name "unconnected-(R0-PadP$3)") (class "Default")
      (node (ref "R0") (pin "P$3") (pinfunction "P$3_P$3") (pintype "passive"))
    )
    (net (code "127") (name "unconnected-(R0-PadP$14)") (class "Default")
      (node (ref "R0") (pin "P$14") (pinfunction "P$14_P$14") (pintype "passive"))
    )
    (net (code "128") (name "unconnected-(R0-PadP$15)") (class "Default")
      (node (ref "R0") (pin "P$15") (pinfunction "P$15_P$15") (pintype "passive"))
    )
    (net (code "129") (name "unconnected-(R0-PadP$16)") (class "Default")
      (node (ref "R0") (pin "P$16") (pinfunction "P$16_P$16") (pintype "passive"))
    )
    (net (code "130") (name "unconnected-(R4-PadP$8)") (class "Default")
      (node (ref "R4") (pin "P$8") (pinfunction "P$8_P$8") (pintype "passive"))
    )
    (net (code "131") (name "unconnected-(U0-2B-PadP$2)") (class "Default")
      (node (ref "U0") (pin "P$2") (pinfunction "2B_P$2") (pintype "bidirectional"))
    )
    (net (code "132") (name "unconnected-(U0-2C-PadP$15)") (class "Default")
      (node (ref "U0") (pin "P$15") (pinfunction "2C_P$15") (pintype "bidirectional"))
    )
    (net (code "133") (name "unconnected-(U0-3B-PadP$3)") (class "Default")
      (node (ref "U0") (pin "P$3") (pinfunction "3B_P$3") (pintype "bidirectional"))
    )
    (net (code "134") (name "unconnected-(U0-3C-PadP$14)") (class "Default")
      (node (ref "U0") (pin "P$14") (pinfunction "3C_P$14") (pintype "bidirectional"))
    )
    (net (code "135") (name "unconnected-(U0-COM-PadP$9)") (class "Default")
      (node (ref "U0") (pin "P$9") (pinfunction "COM_P$9") (pintype "bidirectional"))
    )
    (net (code "136") (name "unconnected-(U1-COM-PadP$9)") (class "Default")
      (node (ref "U1") (pin "P$9") (pinfunction "COM_P$9") (pintype "bidirectional"))
    )
    (net (code "137") (name "unconnected-(U2-COM-PadP$9)") (class "Default")
      (node (ref "U2") (pin "P$9") (pinfunction "COM_P$9") (pintype "bidirectional"))
    )
    (net (code "138") (name "unconnected-(U3-COM-PadP$9)") (class "Default")
      (node (ref "U3") (pin "P$9") (pinfunction "COM_P$9") (pintype "bidirectional"))
    )
    (net (code "139") (name "unconnected-(U4-COM-PadP$9)") (class "Default")
      (node (ref "U4") (pin "P$9") (pinfunction "COM_P$9") (pintype "bidirectional"))
    )
    (net (code "140") (name "unconnected-(U5-COM-PadP$9)") (class "Default")
      (node (ref "U5") (pin "P$9") (pinfunction "COM_P$9") (pintype "bidirectional"))
    )
  )
)
